# Power.net
KiCad netlist of a schematic drawn in Altium Designer
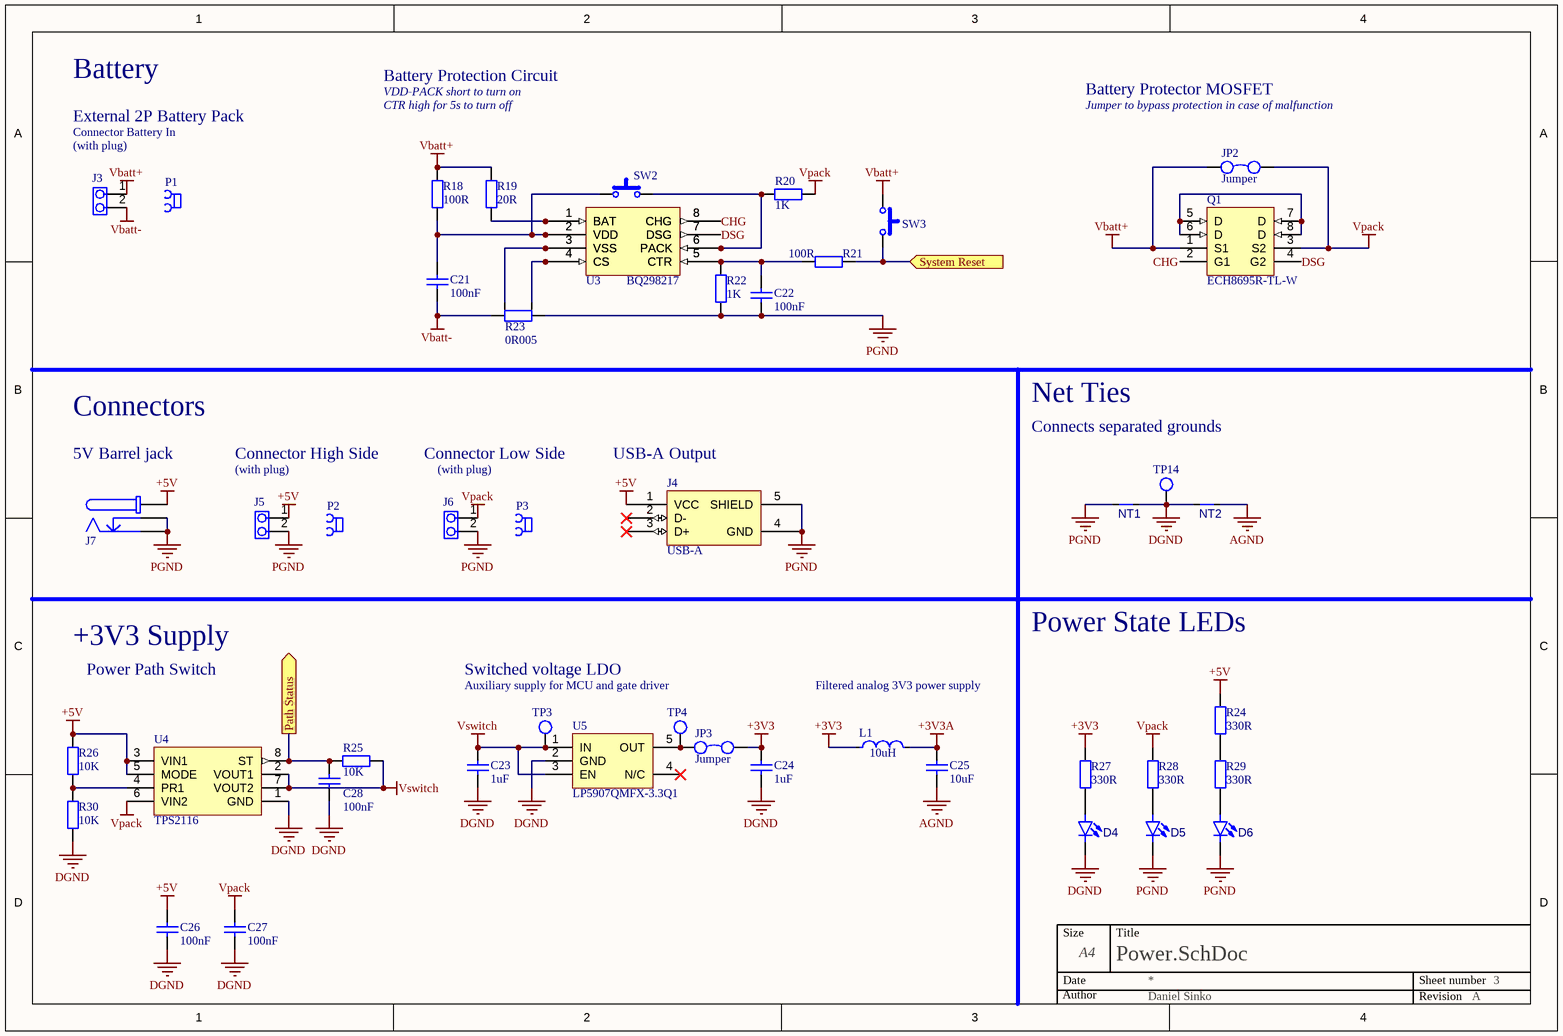
[diagram p0: Power.SchDoc]

(export (version "E")
  (design (tool "Eeschema 10.0.6"))
  (components
    (comp (ref "C21")
      (value "100nF")
      (footprint "CAP0603")
      (fields
        (field (name "MANUFACTURER") "Samsung")
        (field (name "MANUFACTURER PART NUMBER") "CL10B104KA8WPNC")
      )
      (libsource (lib "UPS_Schlib") (part "100nF"))
    )
    (comp (ref "C22")
      (value "100nF")
      (footprint "CAP0603")
      (fields
        (field (name "MANUFACTURER") "Samsung")
        (field (name "MANUFACTURER PART NUMBER") "CL10B104KA8WPNC")
      )
      (libsource (lib "UPS_Schlib") (part "100nF"))
    )
    (comp (ref "C23")
      (value "1uF")
      (footprint "CAP0603")
      (fields
        (field (name "MANUFACTURER") "Walsin Technologies")
        (field (name "MANUFACTURER PART NUMBER") "SH18B105K160CT")
      )
      (libsource (lib "UPS_Schlib") (part "1uF"))
    )
    (comp (ref "C24")
      (value "1uF")
      (footprint "CAP0603")
      (fields
        (field (name "MANUFACTURER") "Walsin Technologies")
        (field (name "MANUFACTURER PART NUMBER") "SH18B105K160CT")
      )
      (libsource (lib "UPS_Schlib") (part "1uF"))
    )
    (comp (ref "C25")
      (value "10uF")
      (footprint "CAP0603")
      (fields
        (field (name "MANUFACTURER") "Samsung")
        (field (name "MANUFACTURER PART NUMBER") "CL10A106MQ8NNND")
      )
      (libsource (lib "UPS_Schlib") (part "10uF"))
    )
    (comp (ref "C26")
      (value "100nF")
      (footprint "CAP0603")
      (fields
        (field (name "MANUFACTURER") "Samsung")
        (field (name "MANUFACTURER PART NUMBER") "CL10B104KA8WPNC")
      )
      (libsource (lib "UPS_Schlib") (part "100nF"))
    )
    (comp (ref "C27")
      (value "100nF")
      (footprint "CAP0603")
      (fields
        (field (name "MANUFACTURER") "Samsung")
        (field (name "MANUFACTURER PART NUMBER") "CL10B104KA8WPNC")
      )
      (libsource (lib "UPS_Schlib") (part "100nF"))
    )
    (comp (ref "C28")
      (value "100nF")
      (footprint "CAP0603")
      (fields
        (field (name "MANUFACTURER") "Samsung")
        (field (name "MANUFACTURER PART NUMBER") "CL10B104KA8WPNC")
      )
      (libsource (lib "UPS_Schlib") (part "100nF"))
    )
    (comp (ref "D4")
      (value "~")
      (footprint "LED0603")
      (description "Single Color LED, Bright Green, Water Clear, 1.1mm")
      (fields
        (field (name "MANUFACTURER") "Wurth Electronics")
        (field (name "MANUFACTURER PART NUMBER") "150060VS75000")
      )
      (libsource (lib "UPS_Schlib") (part "LED Green"))
    )
    (comp (ref "D5")
      (value "~")
      (footprint "LED0603")
      (description "Single Color LED, Bright Green, Water Clear, 1.1mm")
      (fields
        (field (name "MANUFACTURER") "Wurth Electronics")
        (field (name "MANUFACTURER PART NUMBER") "150060VS75000")
      )
      (libsource (lib "UPS_Schlib") (part "LED Green"))
    )
    (comp (ref "D6")
      (value "~")
      (footprint "LED0603")
      (description "Single Color LED, Bright Green, Water Clear, 1.1mm")
      (fields
        (field (name "MANUFACTURER") "Wurth Electronics")
        (field (name "MANUFACTURER PART NUMBER") "150060VS75000")
      )
      (libsource (lib "UPS_Schlib") (part "LED Green"))
    )
    (comp (ref "J3")
      (value "691313510002")
      (footprint "WR-TBL-5.08/2-M")
      (description "Wurth Elektronik, 2 Pin Pluggable Terminal Block, Male")
      (fields
        (field (name "MOUSER PART NUMBER") "710-691313510002")
        (field (name "MANUFACTURER") "Wurth Electronics")
        (field (name "SAFETY APPROVAL") "UL,VDE")
      )
      (libsource (lib "UPS_Schlib") (part "691313510002"))
    )
    (comp (ref "J4")
      (value "USB-A")
      (footprint "USB-A-FEMALE")
      (description "USB Connector")
      (fields (field (name "MANUFACTURER") "Bel") (field (name "MANUFACTURER PART NUMBER") "SS-52100-001"))
      (libsource (lib "UPS_Schlib") (part "USB-A"))
    )
    (comp (ref "J5")
      (value "691313510002")
      (footprint "WR-TBL-5.08/2-M")
      (description "Wurth Elektronik, 2 Pin Pluggable Terminal Block, Male")
      (fields
        (field (name "MOUSER PART NUMBER") "710-691313510002")
        (field (name "MANUFACTURER") "Wurth Electronics")
        (field (name "SAFETY APPROVAL") "UL,VDE")
      )
      (libsource (lib "UPS_Schlib") (part "691313510002"))
    )
    (comp (ref "J6")
      (value "691313510002")
      (footprint "WR-TBL-5.08/2-M")
      (description "Wurth Elektronik, 2 Pin Pluggable Terminal Block, Male")
      (fields
        (field (name "MOUSER PART NUMBER") "710-691313510002")
        (field (name "MANUFACTURER") "Wurth Electronics")
        (field (name "SAFETY APPROVAL") "UL,VDE")
      )
      (libsource (lib "UPS_Schlib") (part "691313510002"))
    )
    (comp (ref "J7")
      (value "DC Power Jack")
      (footprint "DC Power Jack Right Angled")
      (description "CIRCULAR DC POWER CONNECTOR")
      (fields
        (field (name "MANUFACTURER") "Wurth Electronics")
        (field (name "MANUFACTURER PART NUMBER") "694106301002")
      )
      (libsource (lib "UPS_Schlib") (part "DC Power Jack"))
    )
    (comp (ref "JP2")
      (value "Jumper")
      (footprint "PIN-1X2")
      (description "Interconnection Device")
      (fields (field (name "MANUFACTURER") "Harwin") (field (name "MANUFACTURER PART NUMBER") "M7582-46"))
      (libsource (lib "UPS_Schlib") (part "Jumper"))
    )
    (comp (ref "JP3")
      (value "Jumper")
      (footprint "PIN-1X2")
      (description "Interconnection Device")
      (fields (field (name "MANUFACTURER") "Harwin") (field (name "MANUFACTURER PART NUMBER") "M7582-46"))
      (libsource (lib "UPS_Schlib") (part "Jumper"))
    )
    (comp (ref "L1")
      (value "10uH")
      (footprint "IND0603")
      (description "General Purpose Inductor, 10uH, 20%, 1 Element, Ferrite-Core, SMD, 1608M")
      (fields (field (name "MANUFACTURER") "TDK") (field (name "MANUFACTURER PART NUMBER") "MLZ1608E100MT"))
      (libsource (lib "UPS_Schlib") (part "10uH"))
    )
    (comp (ref "NT1")
      (value "NetTie_1-1")
      (footprint "NETTIE_1.85MM")
      (description "NetTie 1 -> 1")
      (libsource (lib "UPS_Schlib") (part "NetTie_1-1"))
    )
    (comp (ref "NT2")
      (value "NetTie_1-1")
      (footprint "NETTIE_1.85MM")
      (description "NetTie 1 -> 1")
      (libsource (lib "UPS_Schlib") (part "NetTie_1-1"))
    )
    (comp (ref "P1")
      (value "691351500002")
      (footprint "WR-TBL-5.08/2-F")
      (description "Wurth Elektronik, 2 Pin Pluggable Terminal Block, Female")
      (fields (field (name "MANUFACTURER") "Wurth Electronics"))
      (libsource (lib "UPS_Schlib") (part "691351500002"))
    )
    (comp (ref "P2")
      (value "691351500002")
      (footprint "WR-TBL-5.08/2-F")
      (description "Wurth Elektronik, 2 Pin Pluggable Terminal Block, Female")
      (fields (field (name "MANUFACTURER") "Wurth Electronics"))
      (libsource (lib "UPS_Schlib") (part "691351500002"))
    )
    (comp (ref "P3")
      (value "691351500002")
      (footprint "WR-TBL-5.08/2-F")
      (description "Wurth Elektronik, 2 Pin Pluggable Terminal Block, Female")
      (fields (field (name "MANUFACTURER") "Wurth Electronics"))
      (libsource (lib "UPS_Schlib") (part "691351500002"))
    )
    (comp (ref "Q1")
      (value "ECH8695R-TL-W")
      (footprint "SOT-28FL")
      (description "Power Field-Effect Transistor, 11A I(D), N-Channel, Metal-oxide Semiconductor FET")
      (fields
        (field (name "MOUSER PART NUMBER") "863-ECH8695R-TL-W")
        (field (name "MANUFACTURER") "ON Semiconductor")
      )
      (libsource (lib "UPS_Schlib") (part "ECH8695R-TL-W"))
    )
    (comp (ref "R18")
      (value "100R")
      (footprint "RES0603")
      (fields
        (field (name "MANUFACTURER") "Yageo")
        (field (name "MANUFACTURER PART NUMBER") "RC0603JR-13100RL")
      )
      (libsource (lib "UPS_Schlib") (part "100R"))
    )
    (comp (ref "R19")
      (value "20R")
      (footprint "RES0603")
      (fields
        (field (name "MANUFACTURER") "Vishay")
        (field (name "MANUFACTURER PART NUMBER") "CRCW060320R0FKEA")
      )
      (libsource (lib "UPS_Schlib") (part "20R"))
    )
    (comp (ref "R20")
      (value "1K")
      (footprint "RES0603")
      (fields
        (field (name "MANUFACTURER") "Bourns")
        (field (name "MANUFACTURER PART NUMBER") "CR0603-FX-1001ELF")
      )
      (libsource (lib "UPS_Schlib") (part "1K"))
    )
    (comp (ref "R21")
      (value "100R")
      (footprint "RES0603")
      (fields
        (field (name "MANUFACTURER") "Yageo")
        (field (name "MANUFACTURER PART NUMBER") "RC0603JR-13100RL")
      )
      (libsource (lib "") (part "100R_1"))
    )
    (comp (ref "R22")
      (value "1K")
      (footprint "RES0603")
      (fields
        (field (name "MANUFACTURER") "Bourns")
        (field (name "MANUFACTURER PART NUMBER") "CR0603-FX-1001ELF")
      )
      (libsource (lib "") (part "1K_1"))
    )
    (comp (ref "R23")
      (value "0R005")
      (footprint "RES1206_KELVIN")
      (description "Resistor Current Sense Metal Foil 1206 5m Ohm 1% 1W ±50ppm/°C T/R")
      (fields
        (field (name "MANUFACTURER") "Eaton")
        (field (name "MANUFACTURER PART NUMBER") "MFSA1206R0050FCM")
      )
      (libsource (lib "UPS_Schlib") (part "0R005"))
    )
    (comp (ref "R24")
      (value "330R")
      (footprint "RES0603")
      (fields
        (field (name "MANUFACTURER") "Walsin Technologies")
        (field (name "MANUFACTURER PART NUMBER") "WR06X3300FTL")
      )
      (libsource (lib "UPS_Schlib") (part "330R"))
    )
    (comp (ref "R25")
      (value "10K")
      (footprint "RES0603")
      (fields
        (field (name "MANUFACTURER") "Bourns")
        (field (name "MANUFACTURER PART NUMBER") "CR0603-FX-1002ELF")
      )
      (libsource (lib "") (part "10K_1"))
    )
    (comp (ref "R26")
      (value "10K")
      (footprint "RES0603")
      (fields
        (field (name "MANUFACTURER") "Bourns")
        (field (name "MANUFACTURER PART NUMBER") "CR0603-FX-1002ELF")
      )
      (libsource (lib "UPS_Schlib") (part "10K"))
    )
    (comp (ref "R27")
      (value "330R")
      (footprint "RES0603")
      (fields
        (field (name "MANUFACTURER") "Walsin Technologies")
        (field (name "MANUFACTURER PART NUMBER") "WR06X3300FTL")
      )
      (libsource (lib "UPS_Schlib") (part "330R"))
    )
    (comp (ref "R28")
      (value "330R")
      (footprint "RES0603")
      (fields
        (field (name "MANUFACTURER") "Walsin Technologies")
        (field (name "MANUFACTURER PART NUMBER") "WR06X3300FTL")
      )
      (libsource (lib "UPS_Schlib") (part "330R"))
    )
    (comp (ref "R29")
      (value "330R")
      (footprint "RES0603")
      (fields
        (field (name "MANUFACTURER") "Walsin Technologies")
        (field (name "MANUFACTURER PART NUMBER") "WR06X3300FTL")
      )
      (libsource (lib "UPS_Schlib") (part "330R"))
    )
    (comp (ref "R30")
      (value "10K")
      (footprint "RES0603")
      (fields
        (field (name "MANUFACTURER") "Bourns")
        (field (name "MANUFACTURER PART NUMBER") "CR0603-FX-1002ELF")
      )
      (libsource (lib "UPS_Schlib") (part "10K"))
    )
    (comp (ref "SW2")
      (value "PTS526 Button")
      (footprint "PTS526 SMG15J SMTR2 LFS")
      (description "PTS526 Series SPST-NO Off-Mom 160 gf Top Actuated J Lead SMT Tactile Switch")
      (fields
        (field (name "MANUFACTURER") "ITT C&K")
        (field (name "MANUFACTURER PART NUMBER") "PTS526SMG15JSMTR2LFS")
      )
      (libsource (lib "UPS_Schlib") (part "PTS526 Button"))
    )
    (comp (ref "SW3")
      (value "PTS526 Button")
      (footprint "PTS526 SMG15J SMTR2 LFS")
      (description "PTS526 Series SPST-NO Off-Mom 160 gf Top Actuated J Lead SMT Tactile Switch")
      (fields
        (field (name "MANUFACTURER") "ITT C&K")
        (field (name "MANUFACTURER PART NUMBER") "PTS526SMG15JSMTR2LFS")
      )
      (libsource (lib "UPS_Schlib") (part "PTS526 Button"))
    )
    (comp (ref "TP3")
      (value "Test Point")
      (footprint "TP-1.5HOLE")
      (libsource (lib "UPS_Schlib") (part "Test Point"))
    )
    (comp (ref "TP4")
      (value "Test Point")
      (footprint "TP-1.5HOLE")
      (libsource (lib "UPS_Schlib") (part "Test Point"))
    )
    (comp (ref "TP14")
      (value "Test Point")
      (footprint "TP-1.5HOLE")
      (libsource (lib "UPS_Schlib") (part "Test Point"))
    )
    (comp (ref "U3")
      (value "BQ298217")
      (footprint "X2QFN-8")
      (fields
        (field (name "MANUFACTURER") "Texas Instruments")
        (field (name "MANUFACTURER PART NUMBER") "BQ298217RUGR")
      )
      (libsource (lib "UPS_Schlib") (part "BQ2980"))
    )
    (comp (ref "U4")
      (value "TPS2116")
      (footprint "SOTFL50P160X60-8N")
      (description "Single-Ended Multiplexer, 1 Func, 2 Channel, PDSO8")
      (fields
        (field (name "MANUFACTURER") "Texas Instruments")
        (field (name "MANUFACTURER PART NUMBER") "TPS2116DRLR")
      )
      (libsource (lib "UPS_Schlib") (part "TPS2116"))
    )
    (comp (ref "U5")
      (value "LP5907QMFX-3.3Q1")
      (footprint "SOT23-5")
      (description "Fixed Positive LDO Regulator, 3.3V, 0.25V Dropout, PDSO5")
      (fields
        (field (name "MOUSER PART NUMBER") "595-LP5907QMFX-3.3Q1")
        (field (name "MANUFACTURER") "Texas Instruments")
      )
      (libsource (lib "UPS_Schlib") (part "LP5907QMFX-3.3Q1"))
    )
  )
  (nets
    (net (code "1") (name "+3V3") (class "Default")
      (node (ref "C24") (pin "2") (pinfunction "2_2") (pintype "passive"))
      (node (ref "JP3") (pin "2") (pintype "passive"))
      (node (ref "L1") (pin "1") (pinfunction "1_1") (pintype "passive"))
      (node (ref "R27") (pin "2") (pinfunction "2_2") (pintype "passive"))
    )
    (net (code "2") (name "+3V3A") (class "Default")
      (node (ref "C25") (pin "2") (pinfunction "2_2") (pintype "passive"))
      (node (ref "L1") (pin "2") (pinfunction "2_2") (pintype "passive"))
    )
    (net (code "3") (name "+5V") (class "Default")
      (node (ref "C26") (pin "2") (pinfunction "2_2") (pintype "passive"))
      (node (ref "J4") (pin "1") (pinfunction "VCC_1") (pintype "power_in"))
      (node (ref "J5") (pin "1") (pinfunction "1_1") (pintype "passive"))
      (node (ref "J7") (pin "1") (pinfunction "1_1") (pintype "passive"))
      (node (ref "R24") (pin "2") (pinfunction "2_2") (pintype "passive"))
      (node (ref "R26") (pin "2") (pinfunction "2_2") (pintype "passive"))
      (node (ref "U4") (pin "3") (pinfunction "VIN1_3") (pintype "passive"))
      (node (ref "U4") (pin "5") (pinfunction "MODE_5") (pintype "passive"))
    )
    (net (code "4") (name "/CHG") (class "Default")
      (node (ref "Q1") (pin "2") (pinfunction "G1_2") (pintype "passive"))
      (node (ref "U3") (pin "8") (pinfunction "CHG_8") (pintype "output"))
    )
    (net (code "5") (name "/DSG") (class "Default")
      (node (ref "Q1") (pin "4") (pinfunction "G2_4") (pintype "passive"))
      (node (ref "U3") (pin "7") (pinfunction "DSG_7") (pintype "output"))
    )
    (net (code "6") (name "/Path Status") (class "Default")
      (node (ref "C28") (pin "2") (pinfunction "2_2") (pintype "passive"))
      (node (ref "R25") (pin "2") (pinfunction "2_2") (pintype "passive"))
      (node (ref "U4") (pin "8") (pinfunction "ST_8") (pintype "output"))
    )
    (net (code "7") (name "/System Reset") (class "Default")
      (node (ref "R21") (pin "2") (pinfunction "2_2") (pintype "passive"))
      (node (ref "SW3") (pin "2") (pinfunction "2_2") (pintype "passive"))
    )
    (net (code "8") (name "AGND") (class "Default")
      (node (ref "C25") (pin "1") (pinfunction "1_1") (pintype "passive"))
      (node (ref "NT2") (pin "2") (pinfunction "2_2") (pintype "passive"))
    )
    (net (code "9") (name "DGND") (class "Default")
      (node (ref "C23") (pin "1") (pinfunction "1_1") (pintype "passive"))
      (node (ref "C24") (pin "1") (pinfunction "1_1") (pintype "passive"))
      (node (ref "C26") (pin "1") (pinfunction "1_1") (pintype "passive"))
      (node (ref "C27") (pin "1") (pinfunction "1_1") (pintype "passive"))
      (node (ref "C28") (pin "1") (pinfunction "1_1") (pintype "passive"))
      (node (ref "D4") (pin "1") (pinfunction "K_1") (pintype "passive"))
      (node (ref "NT1") (pin "2") (pinfunction "2_2") (pintype "passive"))
      (node (ref "NT2") (pin "1") (pinfunction "1_1") (pintype "passive"))
      (node (ref "R30") (pin "1") (pinfunction "1_1") (pintype "passive"))
      (node (ref "TP14") (pin "1") (pintype "passive"))
      (node (ref "U4") (pin "1") (pinfunction "GND_1") (pintype "passive"))
      (node (ref "U5") (pin "2") (pinfunction "GND_2") (pintype "passive"))
    )
    (net (code "10") (name "Net-(D4-A)") (class "Default")
      (node (ref "D4") (pin "2") (pinfunction "A_2") (pintype "passive"))
      (node (ref "R27") (pin "1") (pinfunction "1_1") (pintype "passive"))
    )
    (net (code "11") (name "Net-(D5-A)") (class "Default")
      (node (ref "D5") (pin "2") (pinfunction "A_2") (pintype "passive"))
      (node (ref "R28") (pin "1") (pinfunction "1_1") (pintype "passive"))
    )
    (net (code "12") (name "Net-(D6-A)") (class "Default")
      (node (ref "D6") (pin "2") (pinfunction "A_2") (pintype "passive"))
      (node (ref "R29") (pin "1") (pinfunction "1_1") (pintype "passive"))
    )
    (net (code "13") (name "Net-(Q1-D-Pad5)") (class "Default")
      (node (ref "Q1") (pin "5") (pinfunction "D_5") (pintype "input"))
      (node (ref "Q1") (pin "6") (pinfunction "D_6") (pintype "input"))
      (node (ref "Q1") (pin "7") (pinfunction "D_7") (pintype "input"))
      (node (ref "Q1") (pin "8") (pinfunction "D_8") (pintype "input"))
    )
    (net (code "14") (name "Net-(R24-Pad1)") (class "Default")
      (node (ref "R24") (pin "1") (pinfunction "1_1") (pintype "passive"))
      (node (ref "R29") (pin "2") (pinfunction "2_2") (pintype "passive"))
    )
    (net (code "15") (name "Net-(U3-BAT)") (class "Default")
      (node (ref "R19") (pin "1") (pinfunction "1_1") (pintype "passive"))
      (node (ref "U3") (pin "1") (pinfunction "BAT_1") (pintype "input"))
    )
    (net (code "16") (name "Net-(U3-CS)") (class "Default")
      (node (ref "R23") (pin "4") (pinfunction "4_4") (pintype "passive"))
      (node (ref "U3") (pin "4") (pinfunction "CS_4") (pintype "input"))
    )
    (net (code "17") (name "Net-(U3-CTR)") (class "Default")
      (node (ref "C22") (pin "2") (pinfunction "2_2") (pintype "passive"))
      (node (ref "R21") (pin "1") (pinfunction "1_1") (pintype "passive"))
      (node (ref "R22") (pin "2") (pinfunction "2_2") (pintype "passive"))
      (node (ref "U3") (pin "5") (pinfunction "CTR_5") (pintype "input"))
    )
    (net (code "18") (name "Net-(U3-PACK)") (class "Default")
      (node (ref "R20") (pin "1") (pinfunction "1_1") (pintype "passive"))
      (node (ref "SW2") (pin "2") (pinfunction "2_2") (pintype "passive"))
      (node (ref "U3") (pin "6") (pinfunction "PACK_6") (pintype "input"))
    )
    (net (code "19") (name "Net-(U3-VDD)") (class "Default")
      (node (ref "C21") (pin "2") (pinfunction "2_2") (pintype "passive"))
      (node (ref "R18") (pin "1") (pinfunction "1_1") (pintype "passive"))
      (node (ref "SW2") (pin "1") (pinfunction "1_1") (pintype "passive"))
      (node (ref "U3") (pin "2") (pinfunction "VDD_2") (pintype "power_in"))
    )
    (net (code "20") (name "Net-(U3-VSS)") (class "Default")
      (node (ref "R23") (pin "3") (pinfunction "3_3") (pintype "passive"))
      (node (ref "U3") (pin "3") (pinfunction "VSS_3") (pintype "passive"))
    )
    (net (code "21") (name "Net-(U4-PR1)") (class "Default")
      (node (ref "R26") (pin "1") (pinfunction "1_1") (pintype "passive"))
      (node (ref "R30") (pin "2") (pinfunction "2_2") (pintype "passive"))
      (node (ref "U4") (pin "4") (pinfunction "PR1_4") (pintype "passive"))
    )
    (net (code "22") (name "Net-(U5-OUT)") (class "Default")
      (node (ref "JP3") (pin "1") (pintype "passive"))
      (node (ref "TP4") (pin "1") (pintype "passive"))
      (node (ref "U5") (pin "5") (pinfunction "OUT_5") (pintype "passive"))
    )
    (net (code "23") (name "PGND") (class "Default")
      (node (ref "C22") (pin "1") (pinfunction "1_1") (pintype "passive"))
      (node (ref "D5") (pin "1") (pinfunction "K_1") (pintype "passive"))
      (node (ref "D6") (pin "1") (pinfunction "K_1") (pintype "passive"))
      (node (ref "J4") (pin "4") (pinfunction "GND_4") (pintype "passive"))
      (node (ref "J4") (pin "5") (pinfunction "SHIELD_5") (pintype "passive"))
      (node (ref "J5") (pin "2") (pinfunction "2_2") (pintype "passive"))
      (node (ref "J6") (pin "2") (pinfunction "2_2") (pintype "passive"))
      (node (ref "J7") (pin "2") (pinfunction "2_2") (pintype "passive"))
      (node (ref "J7") (pin "3") (pinfunction "3_3") (pintype "passive"))
      (node (ref "NT1") (pin "1") (pinfunction "1_1") (pintype "passive"))
      (node (ref "R22") (pin "1") (pinfunction "1_1") (pintype "passive"))
      (node (ref "R23") (pin "2") (pinfunction "2_2") (pintype "passive"))
    )
    (net (code "24") (name "Vbatt+") (class "Default")
      (node (ref "J3") (pin "1") (pinfunction "1_1") (pintype "passive"))
      (node (ref "JP2") (pin "1") (pintype "passive"))
      (node (ref "Q1") (pin "1") (pinfunction "S1_1") (pintype "passive"))
      (node (ref "R18") (pin "2") (pinfunction "2_2") (pintype "passive"))
      (node (ref "R19") (pin "2") (pinfunction "2_2") (pintype "passive"))
      (node (ref "SW3") (pin "1") (pinfunction "1_1") (pintype "passive"))
    )
    (net (code "25") (name "Vbatt-") (class "Default")
      (node (ref "C21") (pin "1") (pinfunction "1_1") (pintype "passive"))
      (node (ref "J3") (pin "2") (pinfunction "2_2") (pintype "passive"))
      (node (ref "R23") (pin "1") (pinfunction "1_1") (pintype "passive"))
    )
    (net (code "26") (name "Vpack") (class "Default")
      (node (ref "C27") (pin "2") (pinfunction "2_2") (pintype "passive"))
      (node (ref "J6") (pin "1") (pinfunction "1_1") (pintype "passive"))
      (node (ref "JP2") (pin "2") (pintype "passive"))
      (node (ref "Q1") (pin "3") (pinfunction "S2_3") (pintype "passive"))
      (node (ref "R20") (pin "2") (pinfunction "2_2") (pintype "passive"))
      (node (ref "R28") (pin "2") (pinfunction "2_2") (pintype "passive"))
      (node (ref "U4") (pin "6") (pinfunction "VIN2_6") (pintype "passive"))
    )
    (net (code "27") (name "Vswitch") (class "Default")
      (node (ref "C23") (pin "2") (pinfunction "2_2") (pintype "passive"))
      (node (ref "R25") (pin "1") (pinfunction "1_1") (pintype "passive"))
      (node (ref "TP3") (pin "1") (pintype "passive"))
      (node (ref "U4") (pin "2") (pinfunction "VOUT1_2") (pintype "passive"))
      (node (ref "U4") (pin "7") (pinfunction "VOUT2_7") (pintype "passive"))
      (node (ref "U5") (pin "1") (pinfunction "IN_1") (pintype "passive"))
      (node (ref "U5") (pin "3") (pinfunction "EN_3") (pintype "passive"))
    )
    (net (code "28") (name "unconnected-(J4-D+-Pad3)") (class "Default")
      (node (ref "J4") (pin "3") (pinfunction "D+_3") (pintype "bidirectional+no_connect"))
    )
    (net (code "29") (name "unconnected-(J4-D--Pad2)") (class "Default")
      (node (ref "J4") (pin "2") (pinfunction "D-_2") (pintype "bidirectional+no_connect"))
    )
    (net (code "30") (name "unconnected-(U5-N{slash}C-Pad4)") (class "Default")
      (node (ref "U5") (pin "4") (pinfunction "N/C_4") (pintype "passive+no_connect"))
    )
  )
)
